# Fonte.net
KiCad netlist of a schematic drawn in EAGLE
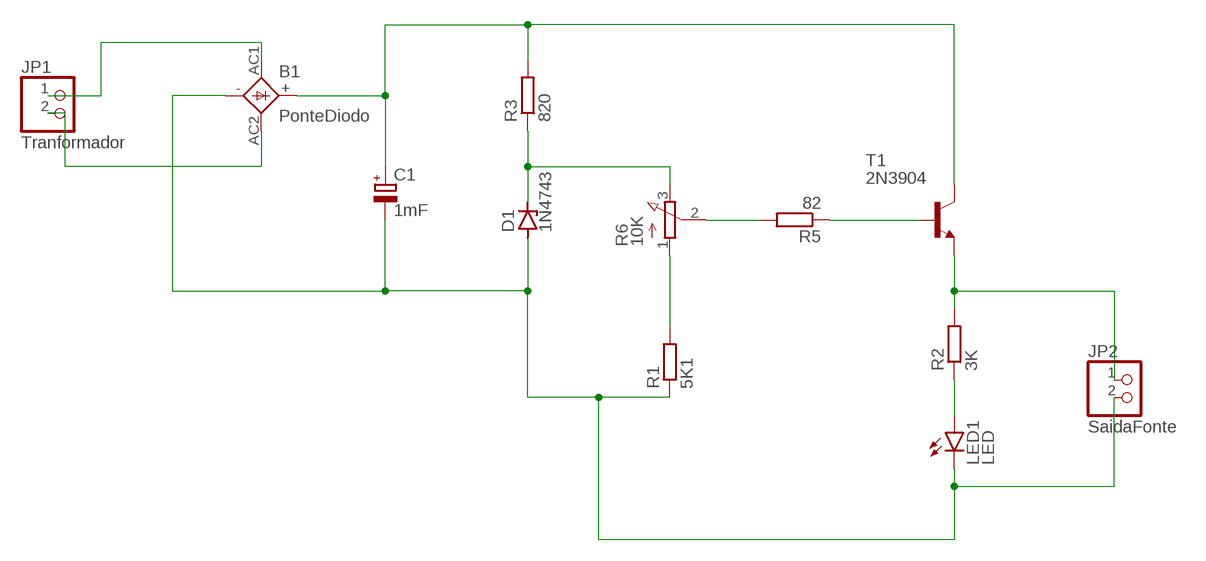
[diagram p0: schematic, sheet 1]

(export (version "E")
  (design (tool "Eeschema 10.0.6"))
  (components
    (comp (ref "B1")
      (value "PonteDiodo")
      (footprint "eagle-import:1KAB")
      (libsource (lib "eagle-import") (part "1KAB"))
    )
    (comp (ref "C1")
      (value "1mF")
      (footprint "eagle-import:E5-10,5")
      (libsource (lib "eagle-import") (part "CPOL-EUE5-10.5"))
    )
    (comp (ref "D1")
      (value "1N4743")
      (footprint "eagle-import:DO41Z10")
      (libsource (lib "eagle-import") (part "1N4728"))
    )
    (comp (ref "JP1")
      (value "Tranformador")
      (footprint "eagle-import:1X02")
      (libsource (lib "eagle-import") (part "PINHD-1X2"))
    )
    (comp (ref "JP2")
      (value "SaidaFonte")
      (footprint "eagle-import:1X02")
      (libsource (lib "eagle-import") (part "PINHD-1X2"))
    )
    (comp (ref "LED1")
      (value "LED")
      (footprint "eagle-import:LED5MM")
      (libsource (lib "eagle-import") (part "LED5MM"))
    )
    (comp (ref "R1")
      (value "5K1")
      (footprint "eagle-import:0204_7")
      (libsource (lib "eagle-import") (part "R-EU_0204/7"))
    )
    (comp (ref "R2")
      (value "3K")
      (footprint "eagle-import:0204_7")
      (libsource (lib "eagle-import") (part "R-EU_0204/7"))
    )
    (comp (ref "R3")
      (value "820")
      (footprint "eagle-import:0204_7")
      (libsource (lib "eagle-import") (part "R-EU_0204/7"))
    )
    (comp (ref "R5")
      (value "82")
      (footprint "eagle-import:0204_7")
      (libsource (lib "eagle-import") (part "R-EU_0204/7"))
    )
    (comp (ref "R6")
      (value "10K")
      (footprint "eagle-import:3RP_1610N")
      (libsource (lib "eagle-import") (part "3RP/1610N"))
    )
    (comp (ref "T1")
      (value "2N3904")
      (footprint "eagle-import:TO92")
      (libsource (lib "eagle-import") (part "2N3904"))
    )
  )
  (nets
    (net (code "1") (name "Net-(B1-PadAC1)") (class "Default")
      (node (ref "B1") (pin "AC1") (pinfunction "AC1_AC1") (pintype "passive"))
      (node (ref "JP1") (pin "1") (pinfunction "1_1") (pintype "passive"))
    )
    (net (code "2") (name "Net-(B1-PadAC2)") (class "Default")
      (node (ref "B1") (pin "AC2") (pinfunction "AC2_AC2") (pintype "passive"))
      (node (ref "JP1") (pin "2") (pinfunction "2_2") (pintype "passive"))
    )
    (net (code "3") (name "Net-(LED1-C)") (class "Default")
      (node (ref "B1") (pin "-") (pinfunction "-_-") (pintype "passive"))
      (node (ref "C1") (pin "-") (pinfunction "-_-") (pintype "passive"))
      (node (ref "D1") (pin "A") (pinfunction "A_A") (pintype "passive"))
      (node (ref "JP2") (pin "2") (pinfunction "2_2") (pintype "passive"))
      (node (ref "LED1") (pin "K") (pinfunction "C_K") (pintype "passive"))
      (node (ref "R1") (pin "1") (pinfunction "1_1") (pintype "passive"))
    )
    (net (code "4") (name "Net-(LED1-PadA)") (class "Default")
      (node (ref "LED1") (pin "A") (pinfunction "A_A") (pintype "passive"))
      (node (ref "R2") (pin "1") (pinfunction "1_1") (pintype "passive"))
    )
    (net (code "5") (name "Net-(R6-A)") (class "Default")
      (node (ref "R1") (pin "2") (pinfunction "2_2") (pintype "passive"))
      (node (ref "R6") (pin "1") (pinfunction "A_1") (pintype "passive"))
    )
    (net (code "6") (name "Net-(R6-E)") (class "Default")
      (node (ref "D1") (pin "C") (pinfunction "C_C") (pintype "passive"))
      (node (ref "R3") (pin "1") (pinfunction "1_1") (pintype "passive"))
      (node (ref "R6") (pin "3") (pinfunction "E_3") (pintype "passive"))
    )
    (net (code "7") (name "Net-(R6-S)") (class "Default")
      (node (ref "R5") (pin "2") (pinfunction "2_2") (pintype "passive"))
      (node (ref "R6") (pin "2") (pinfunction "S_2") (pintype "passive"))
    )
    (net (code "8") (name "Net-(T1-B)") (class "Default")
      (node (ref "R5") (pin "1") (pinfunction "1_1") (pintype "passive"))
      (node (ref "T1") (pin "2") (pinfunction "B_2") (pintype "passive"))
    )
    (net (code "9") (name "Net-(T1-C)") (class "Default")
      (node (ref "B1") (pin "+") (pinfunction "+_+") (pintype "passive"))
      (node (ref "C1") (pin "+") (pinfunction "+_+") (pintype "passive"))
      (node (ref "R3") (pin "2") (pinfunction "2_2") (pintype "passive"))
      (node (ref "T1") (pin "1") (pinfunction "C_1") (pintype "passive"))
    )
    (net (code "10") (name "Net-(T1-E)") (class "Default")
      (node (ref "JP2") (pin "1") (pinfunction "1_1") (pintype "passive"))
      (node (ref "R2") (pin "2") (pinfunction "2_2") (pintype "passive"))
      (node (ref "T1") (pin "3") (pinfunction "E_3") (pintype "passive"))
    )
  )
)
